# bpf-L-band-BP0805.net
KiCad netlist of a schematic drawn in EAGLE
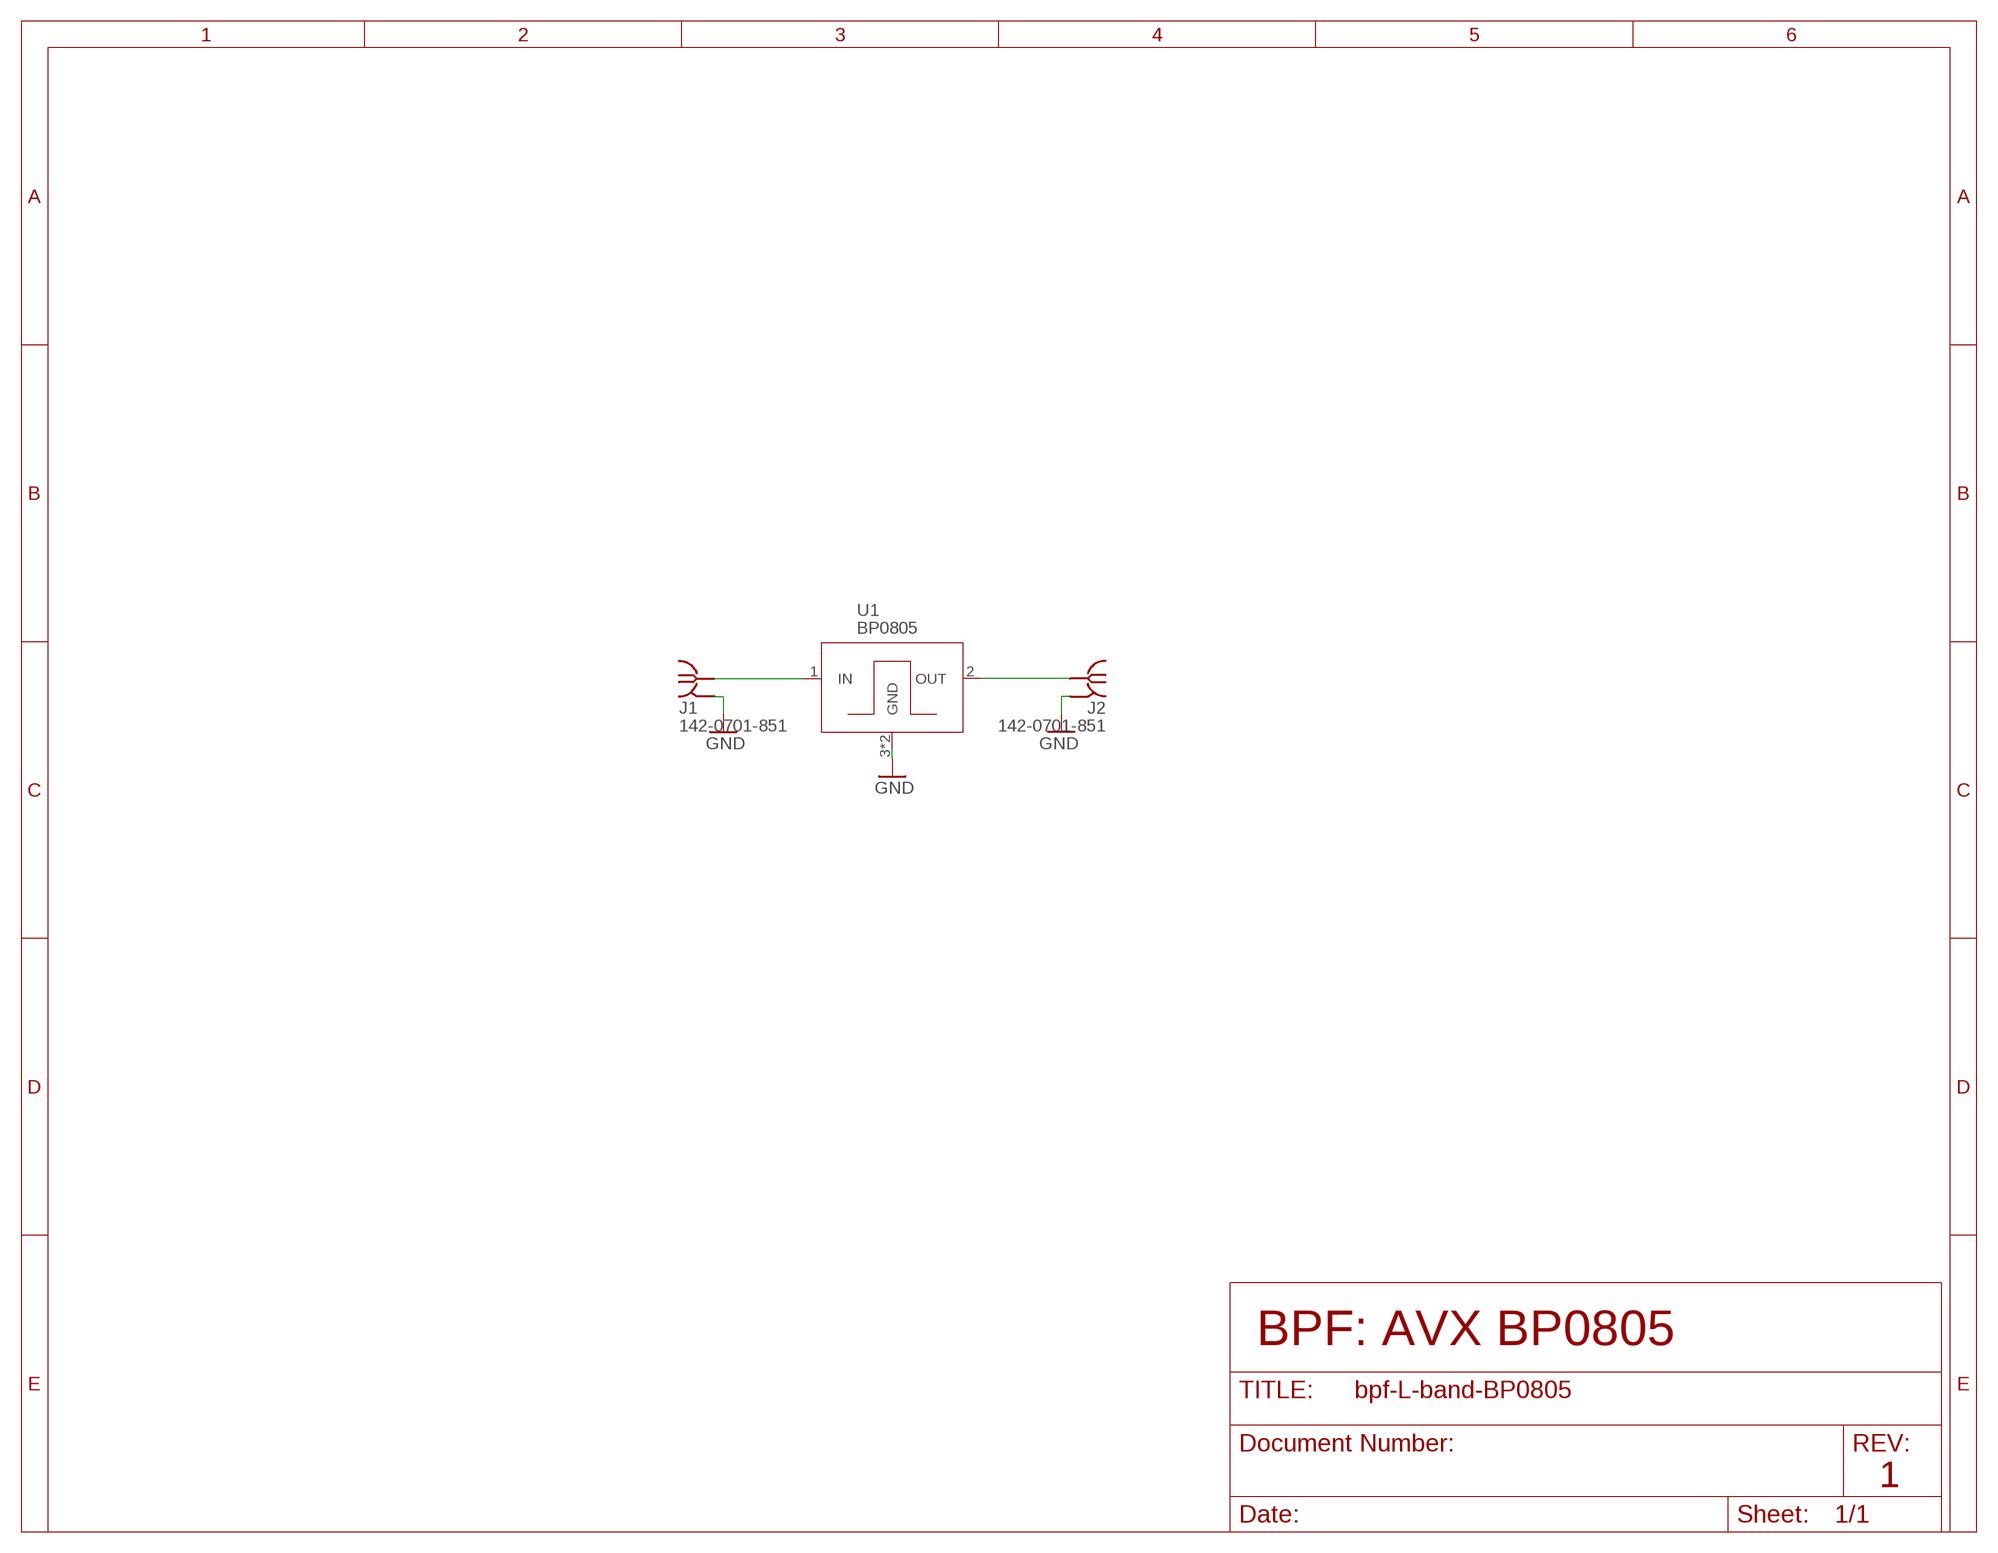
[diagram p0: schematic, sheet 1]

(export (version "E")
  (design (tool "Eeschema 10.0.6"))
  (components
    (comp (ref "J1")
      (value "142-0701-851")
      (footprint "eagle-import:142-0701-851")
      (libsource (lib "eagle-import") (part "142-0701-851"))
    )
    (comp (ref "J2")
      (value "142-0701-851")
      (footprint "eagle-import:142-0701-851")
      (libsource (lib "eagle-import") (part "142-0701-851"))
    )
    (comp (ref "U1")
      (value "BP0805")
      (footprint "eagle-import:BP0805")
      (libsource (lib "eagle-import") (part "BP0805"))
    )
  )
  (nets
    (net (code "1") (name "GND") (class "Default")
      (node (ref "J1") (pin "GND1") (pinfunction "GND_GND1") (pintype "bidirectional"))
      (node (ref "J1") (pin "GND2") (pinfunction "GND_GND2") (pintype "bidirectional"))
      (node (ref "J1") (pin "GND3") (pinfunction "GND_GND3") (pintype "bidirectional"))
      (node (ref "J1") (pin "GND4") (pinfunction "GND_GND4") (pintype "bidirectional"))
      (node (ref "J2") (pin "GND1") (pinfunction "GND_GND1") (pintype "bidirectional"))
      (node (ref "J2") (pin "GND2") (pinfunction "GND_GND2") (pintype "bidirectional"))
      (node (ref "J2") (pin "GND3") (pinfunction "GND_GND3") (pintype "bidirectional"))
      (node (ref "J2") (pin "GND4") (pinfunction "GND_GND4") (pintype "bidirectional"))
      (node (ref "U1") (pin "3") (pinfunction "GND_3") (pintype "power_in"))
      (node (ref "U1") (pin "4") (pinfunction "GND_4") (pintype "power_in"))
    )
    (net (code "2") (name "Net-(J1-RF)") (class "Default")
      (node (ref "J1") (pin "RF1") (pinfunction "RF_RF1") (pintype "bidirectional"))
      (node (ref "U1") (pin "1") (pinfunction "IN_1") (pintype "input"))
    )
    (net (code "3") (name "Net-(J2-RF)") (class "Default")
      (node (ref "J2") (pin "RF1") (pinfunction "RF_RF1") (pintype "bidirectional"))
      (node (ref "U1") (pin "2") (pinfunction "OUT_2") (pintype "output"))
    )
  )
)
